# PCB_NHUNG.net
KiCad netlist of a schematic drawn in Altium Designer
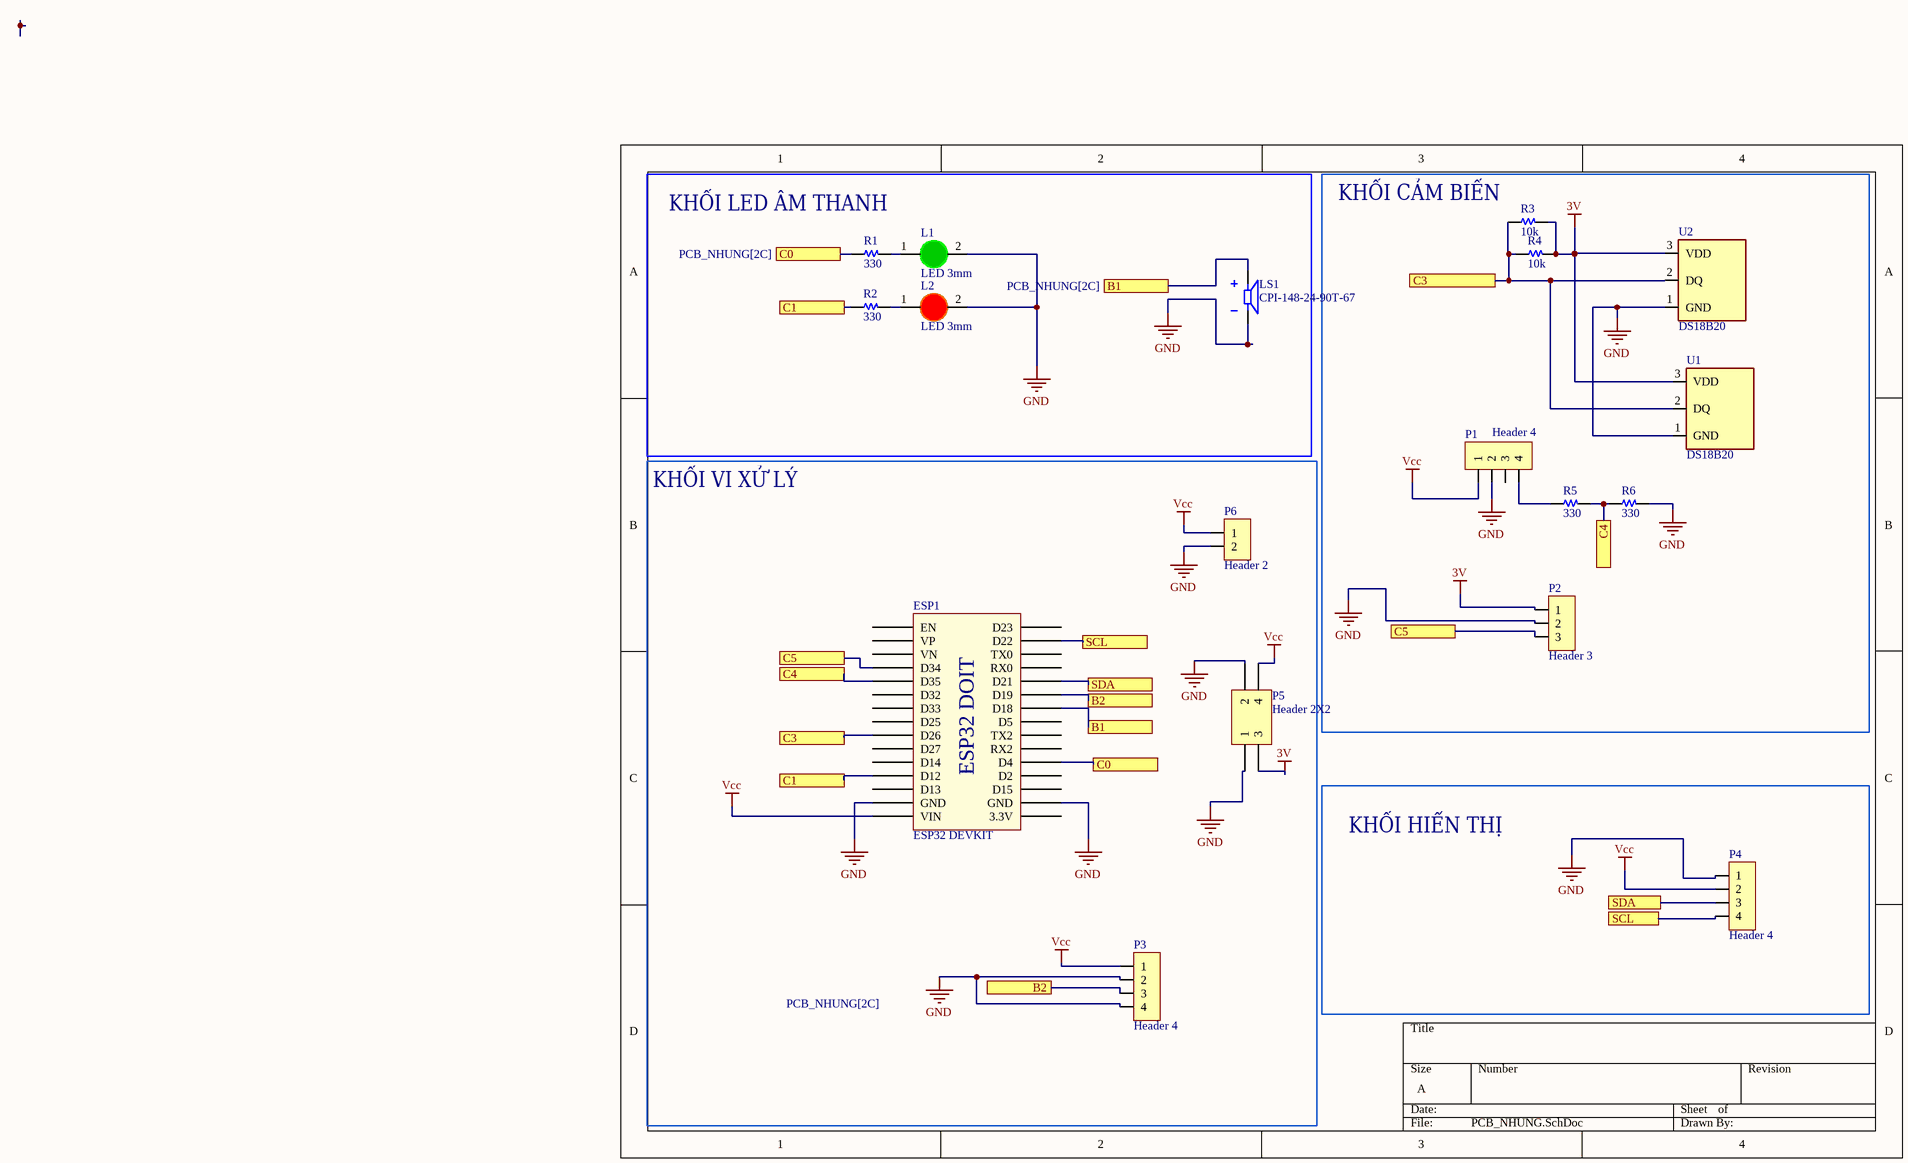
[diagram p0: PCB_NHUNG.SchDoc]

(export (version "E")
  (design (tool "Eeschema 10.0.6"))
  (components
    (comp (ref "ESP1")
      (value "ESP32 DEVKIT")
      (footprint "ESP32 WROOM 32 KIT")
      (libsource (lib "Module") (part "ESP32 WROOM 32 KIT"))
    )
    (comp (ref "L1")
      (value "LED 3mm")
      (footprint "LED-3MM-GREEN")
      (description "Cắm")
      (libsource (lib "Led") (part "LED 3mm Xanh La"))
    )
    (comp (ref "L2")
      (value "LED 3mm")
      (footprint "LED-3MM-RED")
      (description "Cắm")
      (libsource (lib "Led") (part "LED 3mm Do"))
    )
    (comp (ref "LS1")
      (value "CPI-148-24-90T-67")
      (footprint "XDCR_CPI-148-24-90T-67")
      (fields (field (name "MF") "Same Sky"))
      (libsource (lib "CPI-148-24-90T-67") (part "CPI-148-24-90T-67"))
    )
    (comp (ref "P1")
      (value "Header 4")
      (footprint "HDR/Header/4/2mm")
      (description "Header, 4-Pin")
      (libsource (lib "") (part "Header 4_1"))
    )
    (comp (ref "P2")
      (value "Header 3")
      (footprint "HDR/Header/3/2mm")
      (description "Header, 3-Pin")
      (libsource (lib "connectors") (part "Header 3"))
    )
    (comp (ref "P3")
      (value "Header 4")
      (footprint "HDR/Header/4/2mm")
      (description "Header, 4-Pin")
      (libsource (lib "connectors") (part "Header 4"))
    )
    (comp (ref "P4")
      (value "Header 4")
      (footprint "HDR/Header/4/2mm")
      (description "Header, 4-Pin")
      (libsource (lib "connectors") (part "Header 4"))
    )
    (comp (ref "P5")
      (value "Header 2X2")
      (footprint "HDR2X2")
      (description "Header, 2-Pin, Dual row")
      (fields (field (name "PUBLISHER") "Altium Limited"))
      (libsource (lib "Miscellaneous Connectors") (part "Header 2X2"))
    )
    (comp (ref "P6")
      (value "Header 2")
      (footprint "HDR/Header/2/2mm")
      (description "Header, 2-Pin")
      (libsource (lib "connectors") (part "Header 2"))
    )
    (comp (ref "R1")
      (value "330")
      (footprint "R 1/4W/300")
      (description "Resistor")
      (libsource (lib "chipfc_libs") (part "Resistor"))
    )
    (comp (ref "R2")
      (value "330")
      (footprint "R 1/4W/300")
      (description "Resistor")
      (libsource (lib "chipfc_libs") (part "Resistor"))
    )
    (comp (ref "R3")
      (value "10k")
      (footprint "R 1/4W/300")
      (description "Resistor")
      (libsource (lib "chipfc_libs") (part "Resistor"))
    )
    (comp (ref "R4")
      (value "10k")
      (footprint "R 1/4W/300")
      (description "Resistor")
      (libsource (lib "chipfc_libs") (part "Resistor"))
    )
    (comp (ref "R5")
      (value "330")
      (footprint "R 1/4W/300")
      (description "Resistor")
      (libsource (lib "chipfc_libs") (part "Resistor"))
    )
    (comp (ref "R6")
      (value "330")
      (footprint "R 1/4W/300")
      (description "Resistor")
      (libsource (lib "chipfc_libs") (part "Resistor"))
    )
    (comp (ref "U1")
      (value "DS18B20")
      (footprint "TO-92-AMMO")
      (description "Temperature Sensor Digital, Local -55Â°C ~ 125Â°C 12 b 8-uMAX/uSOP")
      (fields (field (name "MF") "Analog Devices"))
      (libsource (lib "DS18B20") (part "DS18B20"))
    )
    (comp (ref "U2")
      (value "DS18B20")
      (footprint "TO-92-AMMO")
      (description "Temperature Sensor Digital, Local -55Â°C ~ 125Â°C 12 b 8-uMAX/uSOP")
      (fields (field (name "MF") "Analog Devices"))
      (libsource (lib "DS18B20") (part "DS18B20"))
    )
  )
  (nets
    (net (code "1") (name "/B1") (class "Default")
      (node (ref "ESP1") (pin "24") (pinfunction "D18_24") (pintype "passive"))
      (node (ref "LS1") (pin "P") (pinfunction "P_P") (pintype "passive"))
    )
    (net (code "2") (name "/B2") (class "Default")
      (node (ref "ESP1") (pin "25") (pinfunction "D19_25") (pintype "passive"))
      (node (ref "P3") (pin "3") (pinfunction "3_3") (pintype "passive"))
    )
    (net (code "3") (name "/C0") (class "Default")
      (node (ref "ESP1") (pin "20") (pinfunction "D4_20") (pintype "passive"))
      (node (ref "R1") (pin "1") (pinfunction "1_1") (pintype "passive"))
    )
    (net (code "4") (name "/C1") (class "Default")
      (node (ref "ESP1") (pin "12") (pinfunction "D12_12") (pintype "passive"))
      (node (ref "R2") (pin "1") (pinfunction "1_1") (pintype "passive"))
    )
    (net (code "5") (name "/C3") (class "Default")
      (node (ref "ESP1") (pin "9") (pinfunction "D26_9") (pintype "passive"))
      (node (ref "R3") (pin "1") (pinfunction "1_1") (pintype "passive"))
      (node (ref "R4") (pin "1") (pinfunction "1_1") (pintype "passive"))
      (node (ref "U1") (pin "2") (pinfunction "DQ_2") (pintype "bidirectional"))
      (node (ref "U2") (pin "2") (pinfunction "DQ_2") (pintype "bidirectional"))
    )
    (net (code "6") (name "/C4") (class "Default")
      (node (ref "ESP1") (pin "5") (pinfunction "D35_5") (pintype "passive"))
      (node (ref "R5") (pin "2") (pinfunction "2_2") (pintype "passive"))
      (node (ref "R6") (pin "1") (pinfunction "1_1") (pintype "passive"))
    )
    (net (code "7") (name "/C5") (class "Default")
      (node (ref "ESP1") (pin "4") (pinfunction "D34_4") (pintype "passive"))
      (node (ref "P2") (pin "3") (pinfunction "3_3") (pintype "passive"))
    )
    (net (code "8") (name "/SCL") (class "Default")
      (node (ref "ESP1") (pin "29") (pinfunction "D22_29") (pintype "passive"))
      (node (ref "P4") (pin "4") (pinfunction "4_4") (pintype "passive"))
    )
    (net (code "9") (name "/SDA") (class "Default")
      (node (ref "ESP1") (pin "26") (pinfunction "D21_26") (pintype "passive"))
      (node (ref "P4") (pin "3") (pinfunction "3_3") (pintype "passive"))
    )
    (net (code "10") (name "3V") (class "Default")
      (node (ref "P2") (pin "1") (pinfunction "1_1") (pintype "passive"))
      (node (ref "P5") (pin "3") (pinfunction "3_3") (pintype "passive"))
      (node (ref "R3") (pin "2") (pinfunction "2_2") (pintype "passive"))
      (node (ref "R4") (pin "2") (pinfunction "2_2") (pintype "passive"))
      (node (ref "U1") (pin "3") (pinfunction "VDD_3") (pintype "power_in"))
      (node (ref "U2") (pin "3") (pinfunction "VDD_3") (pintype "power_in"))
    )
    (net (code "11") (name "GND") (class "Default")
      (node (ref "ESP1") (pin "14") (pinfunction "GND_14") (pintype "passive"))
      (node (ref "ESP1") (pin "17") (pinfunction "GND_17") (pintype "passive"))
      (node (ref "L1") (pin "2") (pinfunction "K_2") (pintype "passive"))
      (node (ref "L2") (pin "2") (pinfunction "K_2") (pintype "passive"))
      (node (ref "LS1") (pin "N") (pinfunction "N_N") (pintype "passive"))
      (node (ref "P1") (pin "2") (pinfunction "2_2") (pintype "passive"))
      (node (ref "P2") (pin "2") (pinfunction "2_2") (pintype "passive"))
      (node (ref "P3") (pin "2") (pinfunction "2_2") (pintype "passive"))
      (node (ref "P3") (pin "4") (pinfunction "4_4") (pintype "passive"))
      (node (ref "P4") (pin "1") (pinfunction "1_1") (pintype "passive"))
      (node (ref "P5") (pin "1") (pinfunction "1_1") (pintype "passive"))
      (node (ref "P5") (pin "2") (pinfunction "2_2") (pintype "passive"))
      (node (ref "P6") (pin "2") (pinfunction "2_2") (pintype "passive"))
      (node (ref "R6") (pin "2") (pinfunction "2_2") (pintype "passive"))
      (node (ref "U1") (pin "1") (pinfunction "GND_1") (pintype "power_in"))
      (node (ref "U2") (pin "1") (pinfunction "GND_1") (pintype "power_in"))
    )
    (net (code "12") (name "Net-(L1-A)") (class "Default")
      (node (ref "L1") (pin "1") (pinfunction "A_1") (pintype "passive"))
      (node (ref "R1") (pin "2") (pinfunction "2_2") (pintype "passive"))
    )
    (net (code "13") (name "Net-(L2-A)") (class "Default")
      (node (ref "L2") (pin "1") (pinfunction "A_1") (pintype "passive"))
      (node (ref "R2") (pin "2") (pinfunction "2_2") (pintype "passive"))
    )
    (net (code "14") (name "Net-(P1-Pad4)") (class "Default")
      (node (ref "P1") (pin "4") (pinfunction "4_4") (pintype "passive"))
      (node (ref "R5") (pin "1") (pinfunction "1_1") (pintype "passive"))
    )
    (net (code "15") (name "Vcc") (class "Default")
      (node (ref "ESP1") (pin "15") (pinfunction "VIN_15") (pintype "passive"))
      (node (ref "P1") (pin "1") (pinfunction "1_1") (pintype "passive"))
      (node (ref "P3") (pin "1") (pinfunction "1_1") (pintype "passive"))
      (node (ref "P4") (pin "2") (pinfunction "2_2") (pintype "passive"))
      (node (ref "P5") (pin "4") (pinfunction "4_4") (pintype "passive"))
      (node (ref "P6") (pin "1") (pinfunction "1_1") (pintype "passive"))
    )
    (net (code "16") (name "unconnected-(ESP1-3.3V-Pad16)") (class "Default")
      (node (ref "ESP1") (pin "16") (pinfunction "3.3V_16") (pintype "passive"))
    )
    (net (code "17") (name "unconnected-(ESP1-D2-Pad19)") (class "Default")
      (node (ref "ESP1") (pin "19") (pinfunction "D2_19") (pintype "passive"))
    )
    (net (code "18") (name "unconnected-(ESP1-D5-Pad23)") (class "Default")
      (node (ref "ESP1") (pin "23") (pinfunction "D5_23") (pintype "passive"))
    )
    (net (code "19") (name "unconnected-(ESP1-D13-Pad13)") (class "Default")
      (node (ref "ESP1") (pin "13") (pinfunction "D13_13") (pintype "passive"))
    )
    (net (code "20") (name "unconnected-(ESP1-D14-Pad11)") (class "Default")
      (node (ref "ESP1") (pin "11") (pinfunction "D14_11") (pintype "passive"))
    )
    (net (code "21") (name "unconnected-(ESP1-D15-Pad18)") (class "Default")
      (node (ref "ESP1") (pin "18") (pinfunction "D15_18") (pintype "passive"))
    )
    (net (code "22") (name "unconnected-(ESP1-D23-Pad30)") (class "Default")
      (node (ref "ESP1") (pin "30") (pinfunction "D23_30") (pintype "passive"))
    )
    (net (code "23") (name "unconnected-(ESP1-D25-Pad8)") (class "Default")
      (node (ref "ESP1") (pin "8") (pinfunction "D25_8") (pintype "passive"))
    )
    (net (code "24") (name "unconnected-(ESP1-D27-Pad10)") (class "Default")
      (node (ref "ESP1") (pin "10") (pinfunction "D27_10") (pintype "passive"))
    )
    (net (code "25") (name "unconnected-(ESP1-D32-Pad6)") (class "Default")
      (node (ref "ESP1") (pin "6") (pinfunction "D32_6") (pintype "passive"))
    )
    (net (code "26") (name "unconnected-(ESP1-D33-Pad7)") (class "Default")
      (node (ref "ESP1") (pin "7") (pinfunction "D33_7") (pintype "passive"))
    )
    (net (code "27") (name "unconnected-(ESP1-EN-Pad1)") (class "Default")
      (node (ref "ESP1") (pin "1") (pinfunction "EN_1") (pintype "passive"))
    )
    (net (code "28") (name "unconnected-(ESP1-RX0-Pad27)") (class "Default")
      (node (ref "ESP1") (pin "27") (pinfunction "RX0_27") (pintype "passive"))
    )
    (net (code "29") (name "unconnected-(ESP1-RX2-Pad21)") (class "Default")
      (node (ref "ESP1") (pin "21") (pinfunction "RX2_21") (pintype "passive"))
    )
    (net (code "30") (name "unconnected-(ESP1-TX0-Pad28)") (class "Default")
      (node (ref "ESP1") (pin "28") (pinfunction "TX0_28") (pintype "passive"))
    )
    (net (code "31") (name "unconnected-(ESP1-TX2-Pad22)") (class "Default")
      (node (ref "ESP1") (pin "22") (pinfunction "TX2_22") (pintype "passive"))
    )
    (net (code "32") (name "unconnected-(ESP1-VN-Pad3)") (class "Default")
      (node (ref "ESP1") (pin "3") (pinfunction "VN_3") (pintype "passive"))
    )
    (net (code "33") (name "unconnected-(ESP1-VP-Pad2)") (class "Default")
      (node (ref "ESP1") (pin "2") (pinfunction "VP_2") (pintype "passive"))
    )
    (net (code "34") (name "unconnected-(P1-Pad3)") (class "Default")
      (node (ref "P1") (pin "3") (pinfunction "3_3") (pintype "passive"))
    )
  )
)
